# ws2812-Breakout.net
KiCad netlist of a schematic drawn in EAGLE
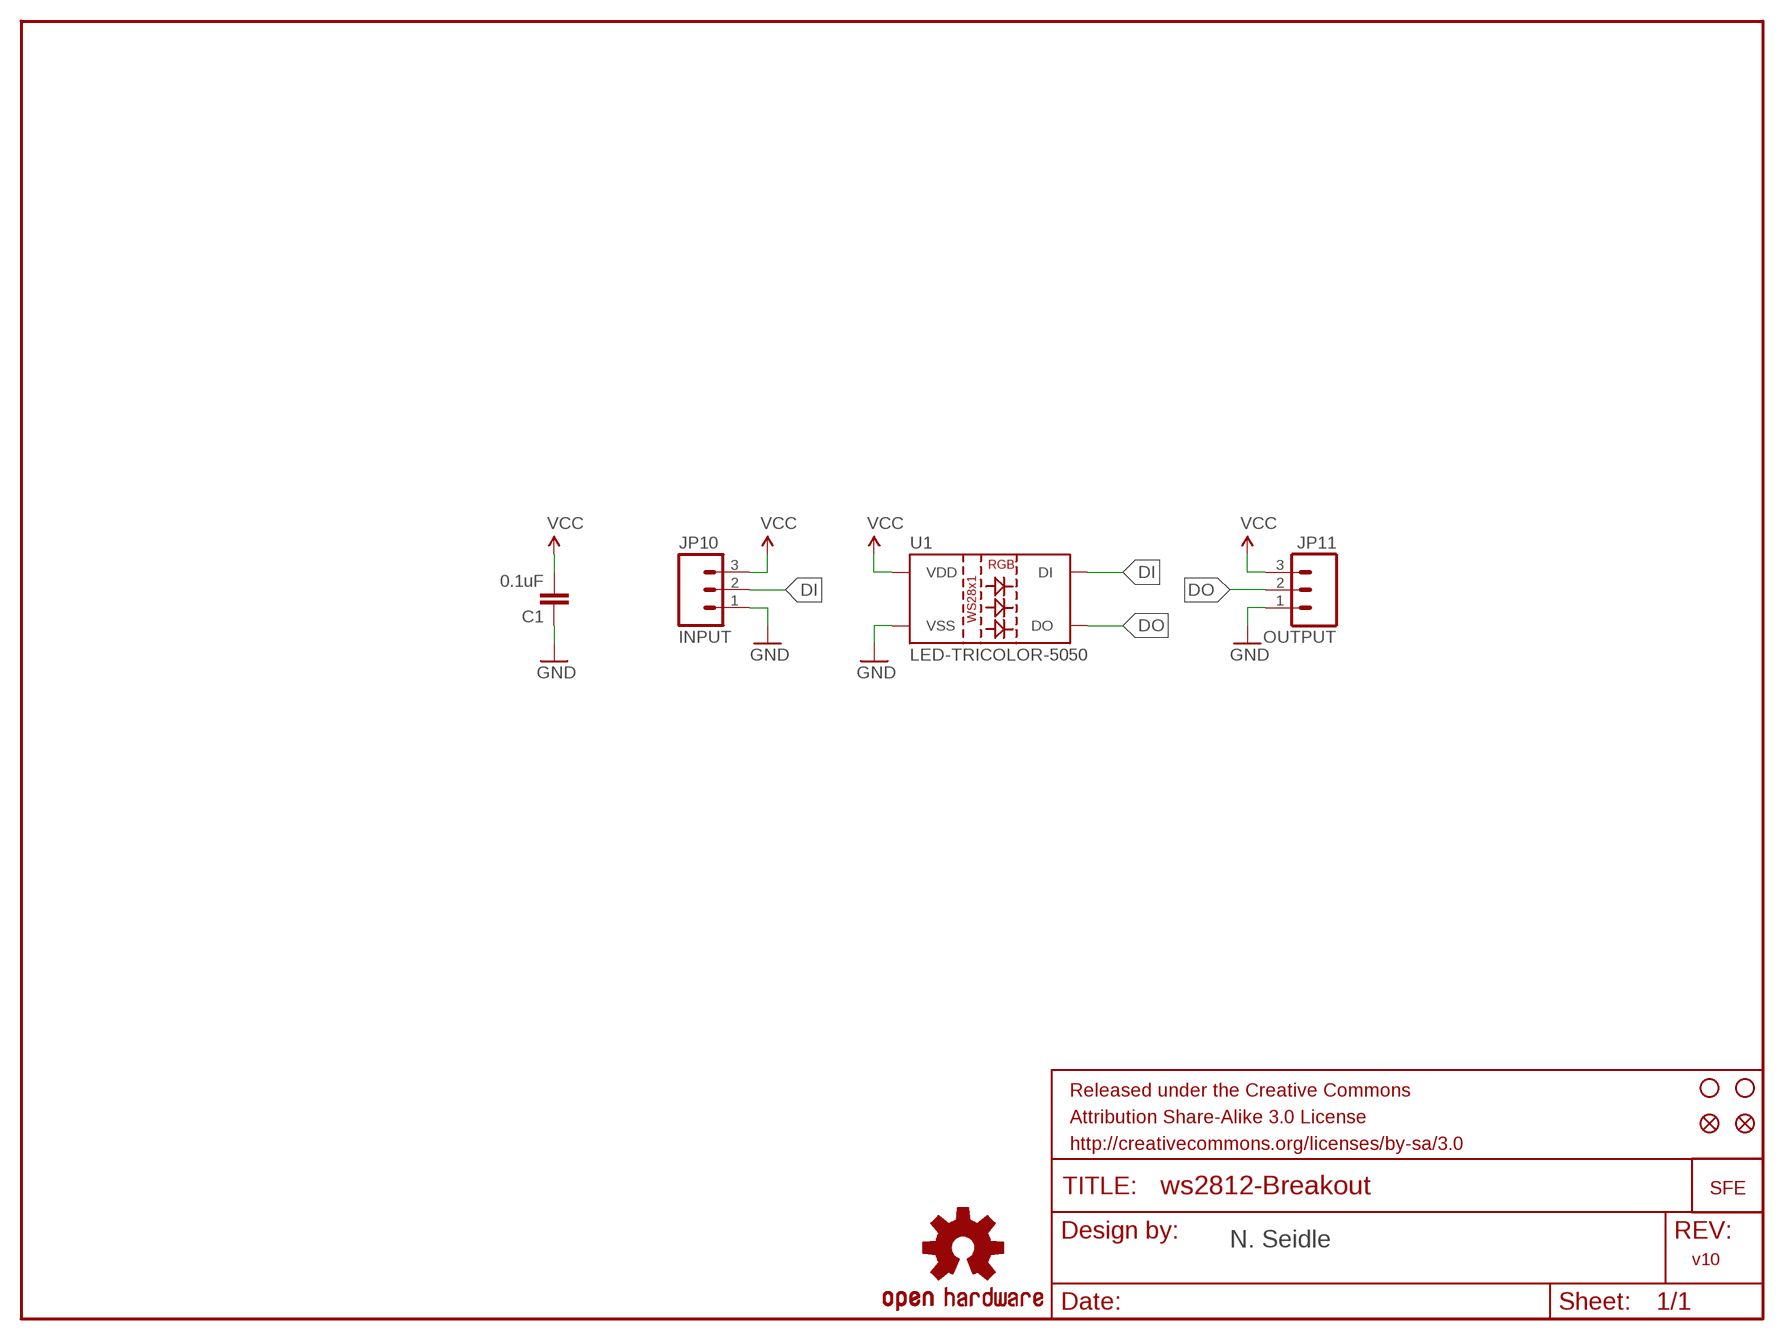
[diagram p0: schematic, sheet 1]

(export (version "E")
  (design (tool "Eeschema 10.0.6"))
  (components
    (comp (ref "C1")
      (value "0.1uF")
      (footprint "eagle-import:0603-CAP")
      (libsource (lib "eagle-import") (part "CAP0603-CAP"))
    )
    (comp (ref "FID1")
      (value "FIDUCIALUFIDUCIAL")
      (footprint "eagle-import:MICRO-FIDUCIAL")
      (libsource (lib "eagle-import") (part "FIDUCIALUFIDUCIAL"))
    )
    (comp (ref "FID2")
      (value "FIDUCIALUFIDUCIAL")
      (footprint "eagle-import:MICRO-FIDUCIAL")
      (libsource (lib "eagle-import") (part "FIDUCIALUFIDUCIAL"))
    )
    (comp (ref "FRAME1")
      (value "FRAME-LETTER")
      (footprint "eagle-import:CREATIVE_COMMONS")
      (libsource (lib "eagle-import") (part "FRAME-LETTER"))
    )
    (comp (ref "JP1")
      (value "STAND-OFF")
      (footprint "eagle-import:STAND-OFF")
      (libsource (lib "eagle-import") (part "STAND-OFF"))
    )
    (comp (ref "JP3")
      (value "LOGO-SFESK")
      (footprint "eagle-import:SFE-LOGO-FLAME")
      (libsource (lib "eagle-import") (part "LOGO-SFESK"))
    )
    (comp (ref "JP4")
      (value "STAND-OFF")
      (footprint "eagle-import:STAND-OFF")
      (libsource (lib "eagle-import") (part "STAND-OFF"))
    )
    (comp (ref "JP10")
      (value "INPUT")
      (footprint "eagle-import:1X03")
      (libsource (lib "eagle-import") (part "M03PTH"))
    )
    (comp (ref "JP11")
      (value "OUTPUT")
      (footprint "eagle-import:1X03")
      (libsource (lib "eagle-import") (part "M03PTH"))
    )
    (comp (ref "LOGO1")
      (value "OSHW-LOGOS")
      (footprint "eagle-import:OSHW-LOGO-S")
      (libsource (lib "eagle-import") (part "OSHW-LOGOS"))
    )
    (comp (ref "U1")
      (value "LED-TRICOLOR-5050")
      (footprint "eagle-import:LED-TRICOLOR-5050-IC")
      (libsource (lib "eagle-import") (part "LED-TRICOLOR-5050-ICWS2811"))
    )
  )
  (nets
    (net (code "1") (name "DI") (class "Default")
      (node (ref "JP10") (pin "2") (pinfunction "2_2") (pintype "passive"))
      (node (ref "U1") (pin "2") (pinfunction "DI_2") (pintype "bidirectional"))
    )
    (net (code "2") (name "DO") (class "Default")
      (node (ref "JP11") (pin "2") (pinfunction "2_2") (pintype "passive"))
      (node (ref "U1") (pin "1") (pinfunction "DO_1") (pintype "bidirectional"))
    )
    (net (code "3") (name "GND") (class "Default")
      (node (ref "C1") (pin "1") (pinfunction "1_1") (pintype "passive"))
      (node (ref "JP10") (pin "1") (pinfunction "1_1") (pintype "passive"))
      (node (ref "JP11") (pin "1") (pinfunction "1_1") (pintype "passive"))
      (node (ref "U1") (pin "6") (pinfunction "VSS_6") (pintype "bidirectional"))
    )
    (net (code "4") (name "VCC") (class "Default")
      (node (ref "C1") (pin "2") (pinfunction "2_2") (pintype "passive"))
      (node (ref "JP10") (pin "3") (pinfunction "3_3") (pintype "passive"))
      (node (ref "JP11") (pin "3") (pinfunction "3_3") (pintype "passive"))
      (node (ref "U1") (pin "3") (pinfunction "VDD_3") (pintype "bidirectional"))
      (node (ref "U1") (pin "5") (pinfunction "VDD_5") (pintype "bidirectional"))
    )
  )
)
